# Powerboard_in_ROV_V1_0.net
KiCad netlist of a schematic drawn in Altium Designer
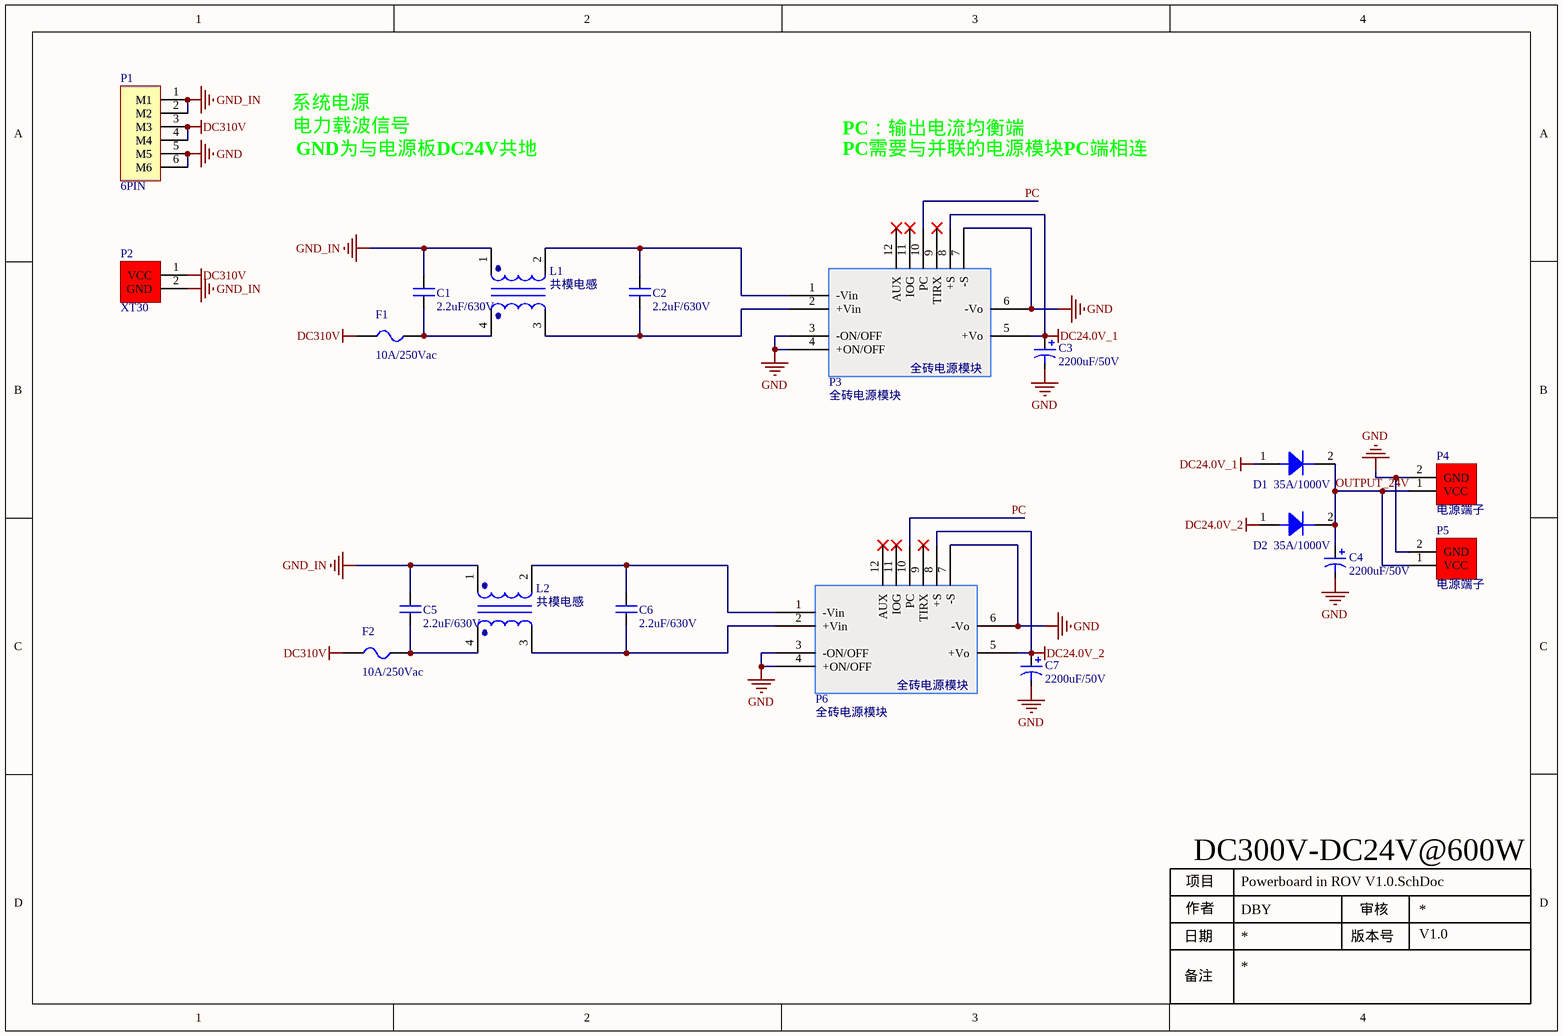
[diagram p0: Powerboard in ROV V1.0.SchDoc]

(export (version "E")
  (design (tool "Eeschema 10.0.6"))
  (components
    (comp (ref "C1")
      (value "2.2uF/630V")
      (footprint "CCB 电容(27mm)")
      (description "无极性CCB电容")
      (libsource (lib "集大电协1.5") (part "Cap2"))
    )
    (comp (ref "C2")
      (value "2.2uF/630V")
      (footprint "CCB 电容(27mm)")
      (description "无极性CCB电容")
      (libsource (lib "集大电协1.5") (part "Cap2"))
    )
    (comp (ref "C3")
      (value "2200uF/50V")
      (footprint "CAP 7.5*16*31.5-H - GD")
      (description "直插极性电容")
      (libsource (lib "集大电协1.5") (part "Cap3"))
    )
    (comp (ref "C4")
      (value "2200uF/50V")
      (footprint "CAP 7.5*16*31.5-H - GD")
      (description "直插极性电容")
      (libsource (lib "集大电协1.5") (part "Cap3"))
    )
    (comp (ref "C5")
      (value "2.2uF/630V")
      (footprint "CCB 电容(27mm)")
      (description "无极性CCB电容")
      (libsource (lib "集大电协1.5") (part "Cap2"))
    )
    (comp (ref "C6")
      (value "2.2uF/630V")
      (footprint "CCB 电容(27mm)")
      (description "无极性CCB电容")
      (libsource (lib "集大电协1.5") (part "Cap2"))
    )
    (comp (ref "C7")
      (value "2200uF/50V")
      (footprint "CAP 7.5*16*31.5-H - GD")
      (description "直插极性电容")
      (libsource (lib "集大电协1.5") (part "Cap3"))
    )
    (comp (ref "D1")
      (value "35A/1000V")
      (footprint "R-6")
      (description "二极管")
      (libsource (lib "集大电协1.5") (part "Diode"))
    )
    (comp (ref "D2")
      (value "35A/1000V")
      (footprint "R-6")
      (description "二极管")
      (libsource (lib "集大电协1.5") (part "Diode"))
    )
    (comp (ref "F1")
      (value "10A/250Vac")
      (footprint "FU 5x20")
      (description "保险丝")
      (libsource (lib "集大电协1.5") (part "Fuse"))
    )
    (comp (ref "F2")
      (value "10A/250Vac")
      (footprint "FU 5x20")
      (description "保险丝")
      (libsource (lib "集大电协1.5") (part "Fuse"))
    )
    (comp (ref "L1") (value "共模电感") (footprint "UU10.5") (libsource (lib "集大电协1.5") (part "共模电感")))
    (comp (ref "L2") (value "共模电感") (footprint "UU10.5") (libsource (lib "集大电协1.5") (part "共模电感")))
    (comp (ref "P1") (value "6PIN") (footprint "PH2.0WS-6P") (libsource (lib "集大电协1.5") (part "接线端子-6PIN")))
    (comp (ref "P2") (value "XT30") (footprint "XT30PW-F") (libsource (lib "") (part "电源端子_1")))
    (comp (ref "P3") (value "全砖电源模块") (footprint "全砖电源模块") (libsource (lib "集大电协1.5") (part "全砖电源模块（迪龙）")))
    (comp (ref "P4") (value "电源端子") (footprint "XT60PW-F") (libsource (lib "集大电协1.5") (part "电源端子")))
    (comp (ref "P5") (value "电源端子") (footprint "XT60PW-F") (libsource (lib "集大电协1.5") (part "电源端子")))
    (comp (ref "P6") (value "全砖电源模块") (footprint "全砖电源模块") (libsource (lib "集大电协1.5") (part "全砖电源模块（迪龙）")))
  )
  (nets
    (net (code "1") (name "/OUTPUT_24V") (class "Default")
      (node (ref "C4") (pin "1") (pinfunction "1_1") (pintype "passive"))
      (node (ref "D1") (pin "2") (pinfunction "2_2") (pintype "passive"))
      (node (ref "D2") (pin "2") (pinfunction "2_2") (pintype "passive"))
      (node (ref "P4") (pin "1") (pinfunction "VCC_1") (pintype "passive"))
      (node (ref "P5") (pin "1") (pinfunction "VCC_1") (pintype "passive"))
    )
    (net (code "2") (name "/PC") (class "Default")
      (node (ref "P3") (pin "10") (pinfunction "PC_10") (pintype "passive"))
      (node (ref "P6") (pin "10") (pinfunction "PC_10") (pintype "passive"))
    )
    (net (code "3") (name "DC24.0V_1") (class "Default")
      (node (ref "C3") (pin "1") (pinfunction "1_1") (pintype "passive"))
      (node (ref "D1") (pin "1") (pintype "passive"))
      (node (ref "P3") (pin "5") (pinfunction "+Vo_5") (pintype "passive"))
      (node (ref "P3") (pin "8") (pinfunction "+S_8") (pintype "passive"))
    )
    (net (code "4") (name "DC24.0V_2") (class "Default")
      (node (ref "C7") (pin "1") (pinfunction "1_1") (pintype "passive"))
      (node (ref "D2") (pin "1") (pintype "passive"))
      (node (ref "P6") (pin "5") (pinfunction "+Vo_5") (pintype "passive"))
      (node (ref "P6") (pin "8") (pinfunction "+S_8") (pintype "passive"))
    )
    (net (code "5") (name "DC310V") (class "Default")
      (node (ref "F1") (pin "1") (pinfunction "1_1") (pintype "passive"))
      (node (ref "F2") (pin "1") (pinfunction "1_1") (pintype "passive"))
      (node (ref "P1") (pin "3") (pinfunction "M3_3") (pintype "passive"))
      (node (ref "P1") (pin "4") (pinfunction "M4_4") (pintype "passive"))
      (node (ref "P2") (pin "1") (pinfunction "VCC_1") (pintype "passive"))
    )
    (net (code "6") (name "GND") (class "Default")
      (node (ref "C3") (pin "2") (pinfunction "2_2") (pintype "passive"))
      (node (ref "C4") (pin "2") (pinfunction "2_2") (pintype "passive"))
      (node (ref "C7") (pin "2") (pinfunction "2_2") (pintype "passive"))
      (node (ref "P1") (pin "5") (pinfunction "M5_5") (pintype "passive"))
      (node (ref "P1") (pin "6") (pinfunction "M6_6") (pintype "passive"))
      (node (ref "P3") (pin "3") (pinfunction "-ON/OFF_3") (pintype "passive"))
      (node (ref "P3") (pin "4") (pinfunction "+ON/OFF_4") (pintype "passive"))
      (node (ref "P3") (pin "6") (pinfunction "-Vo_6") (pintype "passive"))
      (node (ref "P3") (pin "7") (pinfunction "-S_7") (pintype "passive"))
      (node (ref "P4") (pin "2") (pinfunction "GND_2") (pintype "passive"))
      (node (ref "P5") (pin "2") (pinfunction "GND_2") (pintype "passive"))
      (node (ref "P6") (pin "3") (pinfunction "-ON/OFF_3") (pintype "passive"))
      (node (ref "P6") (pin "4") (pinfunction "+ON/OFF_4") (pintype "passive"))
      (node (ref "P6") (pin "6") (pinfunction "-Vo_6") (pintype "passive"))
      (node (ref "P6") (pin "7") (pinfunction "-S_7") (pintype "passive"))
    )
    (net (code "7") (name "GND_IN") (class "Default")
      (node (ref "C1") (pin "1") (pinfunction "1_1") (pintype "passive"))
      (node (ref "C5") (pin "1") (pinfunction "1_1") (pintype "passive"))
      (node (ref "L1") (pin "1") (pinfunction "1_1") (pintype "passive"))
      (node (ref "L2") (pin "1") (pinfunction "1_1") (pintype "passive"))
      (node (ref "P1") (pin "1") (pinfunction "M1_1") (pintype "passive"))
      (node (ref "P1") (pin "2") (pinfunction "M2_2") (pintype "passive"))
      (node (ref "P2") (pin "2") (pinfunction "GND_2") (pintype "passive"))
    )
    (net (code "8") (name "Net-(C1-Pad2)") (class "Default")
      (node (ref "C1") (pin "2") (pinfunction "2_2") (pintype "passive"))
      (node (ref "F1") (pin "2") (pinfunction "2_2") (pintype "passive"))
      (node (ref "L1") (pin "4") (pinfunction "4_4") (pintype "passive"))
    )
    (net (code "9") (name "Net-(C5-Pad2)") (class "Default")
      (node (ref "C5") (pin "2") (pinfunction "2_2") (pintype "passive"))
      (node (ref "F2") (pin "2") (pinfunction "2_2") (pintype "passive"))
      (node (ref "L2") (pin "4") (pinfunction "4_4") (pintype "passive"))
    )
    (net (code "10") (name "Net-(P3-+Vin)") (class "Default")
      (node (ref "C2") (pin "1") (pinfunction "1_1") (pintype "passive"))
      (node (ref "L1") (pin "3") (pinfunction "3_3") (pintype "passive"))
      (node (ref "P3") (pin "2") (pinfunction "+Vin_2") (pintype "passive"))
    )
    (net (code "11") (name "Net-(P3--Vin)") (class "Default")
      (node (ref "C2") (pin "2") (pinfunction "2_2") (pintype "passive"))
      (node (ref "L1") (pin "2") (pinfunction "2_2") (pintype "passive"))
      (node (ref "P3") (pin "1") (pinfunction "-Vin_1") (pintype "passive"))
    )
    (net (code "12") (name "Net-(P6-+Vin)") (class "Default")
      (node (ref "C6") (pin "1") (pinfunction "1_1") (pintype "passive"))
      (node (ref "L2") (pin "3") (pinfunction "3_3") (pintype "passive"))
      (node (ref "P6") (pin "2") (pinfunction "+Vin_2") (pintype "passive"))
    )
    (net (code "13") (name "Net-(P6--Vin)") (class "Default")
      (node (ref "C6") (pin "2") (pinfunction "2_2") (pintype "passive"))
      (node (ref "L2") (pin "2") (pinfunction "2_2") (pintype "passive"))
      (node (ref "P6") (pin "1") (pinfunction "-Vin_1") (pintype "passive"))
    )
    (net (code "14") (name "unconnected-(P3-AUX-Pad12)") (class "Default")
      (node (ref "P3") (pin "12") (pinfunction "AUX_12") (pintype "passive+no_connect"))
    )
    (net (code "15") (name "unconnected-(P3-IOG-Pad11)") (class "Default")
      (node (ref "P3") (pin "11") (pinfunction "IOG_11") (pintype "passive+no_connect"))
    )
    (net (code "16") (name "unconnected-(P3-TIRX-Pad9)") (class "Default")
      (node (ref "P3") (pin "9") (pinfunction "TIRX_9") (pintype "passive+no_connect"))
    )
    (net (code "17") (name "unconnected-(P6-AUX-Pad12)") (class "Default")
      (node (ref "P6") (pin "12") (pinfunction "AUX_12") (pintype "passive+no_connect"))
    )
    (net (code "18") (name "unconnected-(P6-IOG-Pad11)") (class "Default")
      (node (ref "P6") (pin "11") (pinfunction "IOG_11") (pintype "passive+no_connect"))
    )
    (net (code "19") (name "unconnected-(P6-TIRX-Pad9)") (class "Default")
      (node (ref "P6") (pin "9") (pinfunction "TIRX_9") (pintype "passive+no_connect"))
    )
  )
)
